# Chov2_led.net
KiCad netlist of a schematic drawn in Altium Designer
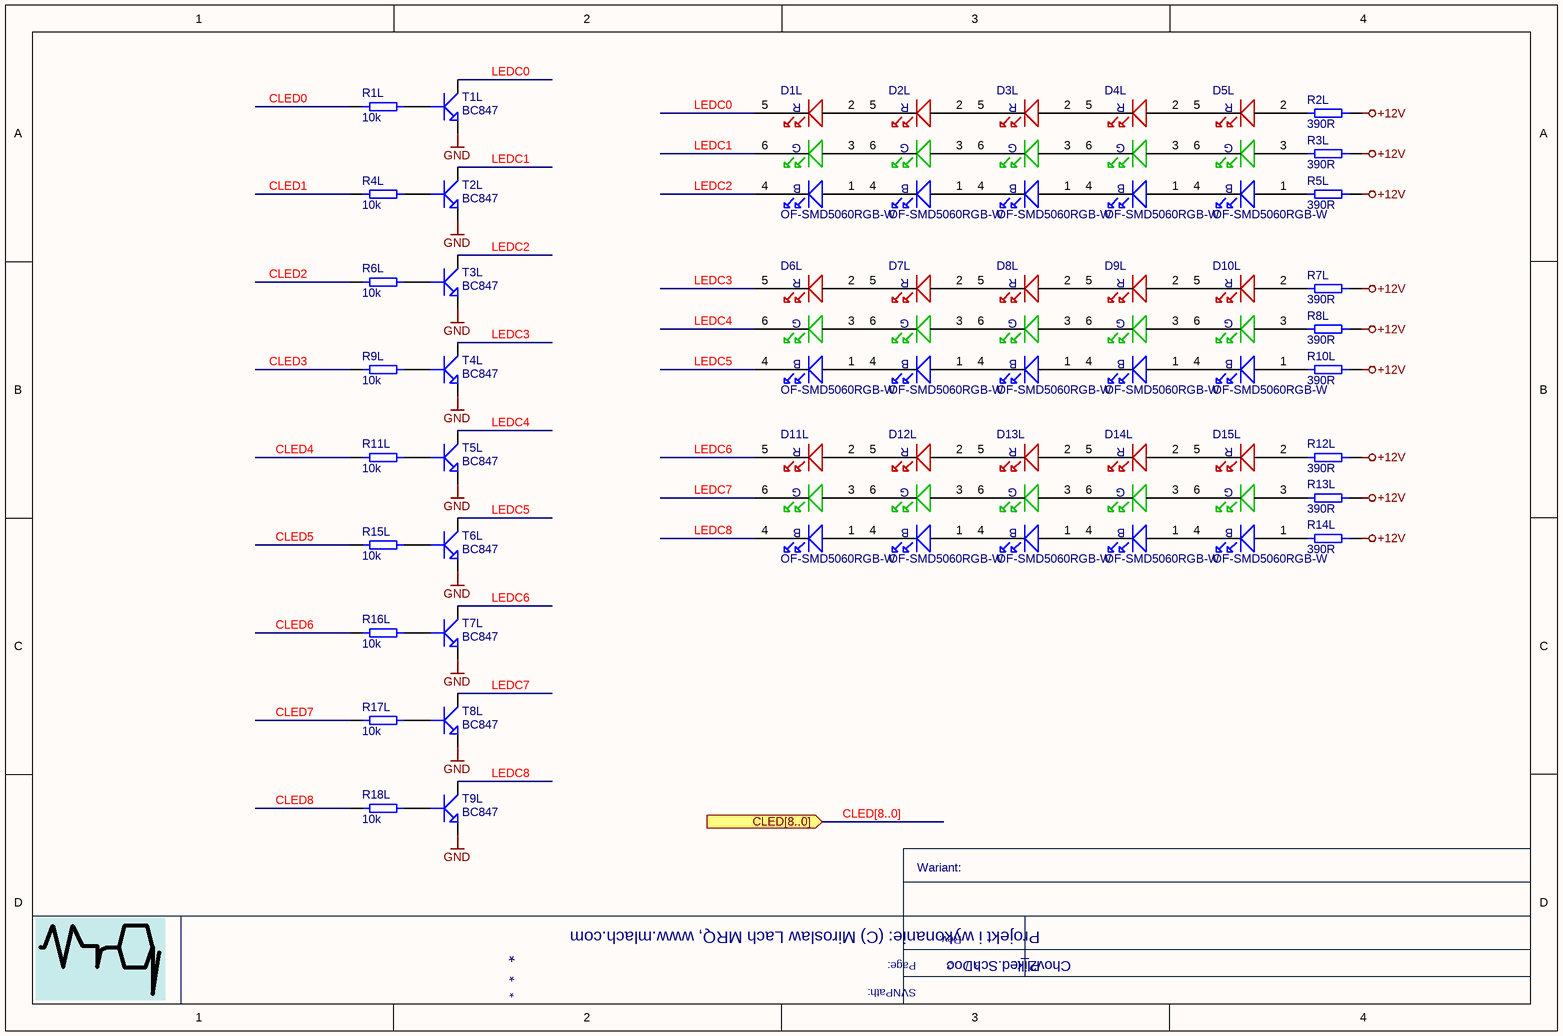
[diagram p0: Chov2_led.SchDoc]

(export (version "E")
  (design (tool "Eeschema 10.0.6"))
  (components
    (comp (ref "D1L")
      (value "OF-SMD5060RGB-W")
      (footprint "OF-SMD5060RGB-W")
      (libsource (lib "Parts") (part "OF-SMD5060RGB-W"))
    )
    (comp (ref "D2L")
      (value "OF-SMD5060RGB-W")
      (footprint "OF-SMD5060RGB-W")
      (libsource (lib "Parts") (part "OF-SMD5060RGB-W"))
    )
    (comp (ref "D3L")
      (value "OF-SMD5060RGB-W")
      (footprint "OF-SMD5060RGB-W")
      (libsource (lib "Parts") (part "OF-SMD5060RGB-W"))
    )
    (comp (ref "D4L")
      (value "OF-SMD5060RGB-W")
      (footprint "OF-SMD5060RGB-W")
      (libsource (lib "Parts") (part "OF-SMD5060RGB-W"))
    )
    (comp (ref "D5L")
      (value "OF-SMD5060RGB-W")
      (footprint "OF-SMD5060RGB-W")
      (libsource (lib "Parts") (part "OF-SMD5060RGB-W"))
    )
    (comp (ref "D6L")
      (value "OF-SMD5060RGB-W")
      (footprint "OF-SMD5060RGB-W")
      (libsource (lib "Parts") (part "OF-SMD5060RGB-W"))
    )
    (comp (ref "D7L")
      (value "OF-SMD5060RGB-W")
      (footprint "OF-SMD5060RGB-W")
      (libsource (lib "Parts") (part "OF-SMD5060RGB-W"))
    )
    (comp (ref "D8L")
      (value "OF-SMD5060RGB-W")
      (footprint "OF-SMD5060RGB-W")
      (libsource (lib "Parts") (part "OF-SMD5060RGB-W"))
    )
    (comp (ref "D9L")
      (value "OF-SMD5060RGB-W")
      (footprint "OF-SMD5060RGB-W")
      (libsource (lib "Parts") (part "OF-SMD5060RGB-W"))
    )
    (comp (ref "D10L")
      (value "OF-SMD5060RGB-W")
      (footprint "OF-SMD5060RGB-W")
      (libsource (lib "Parts") (part "OF-SMD5060RGB-W"))
    )
    (comp (ref "D11L")
      (value "OF-SMD5060RGB-W")
      (footprint "OF-SMD5060RGB-W")
      (libsource (lib "Parts") (part "OF-SMD5060RGB-W"))
    )
    (comp (ref "D12L")
      (value "OF-SMD5060RGB-W")
      (footprint "OF-SMD5060RGB-W")
      (libsource (lib "Parts") (part "OF-SMD5060RGB-W"))
    )
    (comp (ref "D13L")
      (value "OF-SMD5060RGB-W")
      (footprint "OF-SMD5060RGB-W")
      (libsource (lib "Parts") (part "OF-SMD5060RGB-W"))
    )
    (comp (ref "D14L")
      (value "OF-SMD5060RGB-W")
      (footprint "OF-SMD5060RGB-W")
      (libsource (lib "Parts") (part "OF-SMD5060RGB-W"))
    )
    (comp (ref "D15L")
      (value "OF-SMD5060RGB-W")
      (footprint "OF-SMD5060RGB-W")
      (libsource (lib "Parts") (part "OF-SMD5060RGB-W"))
    )
    (comp (ref "R1L")
      (value "0603WGF10KT5E")
      (footprint "0603-IPC")
      (fields (field (name "OTHERPARAMS") "10k") (field (name "TOLERANCE") "1%"))
      (libsource (lib "Parts") (part "R"))
    )
    (comp (ref "R2L")
      (value "0805WAF 390R T5E")
      (footprint "0805")
      (fields (field (name "OTHERPARAMS") "390R") (field (name "TOLERANCE") "1%"))
      (libsource (lib "Parts") (part "R"))
    )
    (comp (ref "R3L")
      (value "0805WAF 390R T5E")
      (footprint "0805")
      (fields (field (name "OTHERPARAMS") "390R") (field (name "TOLERANCE") "1%"))
      (libsource (lib "Parts") (part "R"))
    )
    (comp (ref "R4L")
      (value "0603WGF10KT5E")
      (footprint "0603-IPC")
      (fields (field (name "OTHERPARAMS") "10k") (field (name "TOLERANCE") "1%"))
      (libsource (lib "Parts") (part "R"))
    )
    (comp (ref "R5L")
      (value "0805WAF 390R T5E")
      (footprint "0805")
      (fields (field (name "OTHERPARAMS") "390R") (field (name "TOLERANCE") "1%"))
      (libsource (lib "Parts") (part "R"))
    )
    (comp (ref "R6L")
      (value "0603WGF10KT5E")
      (footprint "0603-IPC")
      (fields (field (name "OTHERPARAMS") "10k") (field (name "TOLERANCE") "1%"))
      (libsource (lib "Parts") (part "R"))
    )
    (comp (ref "R7L")
      (value "0805WAF 390R T5E")
      (footprint "0805")
      (fields (field (name "OTHERPARAMS") "390R") (field (name "TOLERANCE") "1%"))
      (libsource (lib "Parts") (part "R"))
    )
    (comp (ref "R8L")
      (value "0805WAF 390R T5E")
      (footprint "0805")
      (fields (field (name "OTHERPARAMS") "390R") (field (name "TOLERANCE") "1%"))
      (libsource (lib "Parts") (part "R"))
    )
    (comp (ref "R9L")
      (value "0603WGF10KT5E")
      (footprint "0603-IPC")
      (fields (field (name "OTHERPARAMS") "10k") (field (name "TOLERANCE") "1%"))
      (libsource (lib "Parts") (part "R"))
    )
    (comp (ref "R10L")
      (value "0805WAF 390R T5E")
      (footprint "0805")
      (fields (field (name "OTHERPARAMS") "390R") (field (name "TOLERANCE") "1%"))
      (libsource (lib "Parts") (part "R"))
    )
    (comp (ref "R11L")
      (value "0603WGF10KT5E")
      (footprint "0603-IPC")
      (fields (field (name "OTHERPARAMS") "10k") (field (name "TOLERANCE") "1%"))
      (libsource (lib "Parts") (part "R"))
    )
    (comp (ref "R12L")
      (value "0805WAF 390R T5E")
      (footprint "0805")
      (fields (field (name "OTHERPARAMS") "390R") (field (name "TOLERANCE") "1%"))
      (libsource (lib "Parts") (part "R"))
    )
    (comp (ref "R13L")
      (value "0805WAF 390R T5E")
      (footprint "0805")
      (fields (field (name "OTHERPARAMS") "390R") (field (name "TOLERANCE") "1%"))
      (libsource (lib "Parts") (part "R"))
    )
    (comp (ref "R14L")
      (value "0805WAF 390R T5E")
      (footprint "0805")
      (fields (field (name "OTHERPARAMS") "390R") (field (name "TOLERANCE") "1%"))
      (libsource (lib "Parts") (part "R"))
    )
    (comp (ref "R15L")
      (value "0603WGF10KT5E")
      (footprint "0603-IPC")
      (fields (field (name "OTHERPARAMS") "10k") (field (name "TOLERANCE") "1%"))
      (libsource (lib "Parts") (part "R"))
    )
    (comp (ref "R16L")
      (value "0603WGF10KT5E")
      (footprint "0603-IPC")
      (fields (field (name "OTHERPARAMS") "10k") (field (name "TOLERANCE") "1%"))
      (libsource (lib "Parts") (part "R"))
    )
    (comp (ref "R17L")
      (value "0603WGF10KT5E")
      (footprint "0603-IPC")
      (fields (field (name "OTHERPARAMS") "10k") (field (name "TOLERANCE") "1%"))
      (libsource (lib "Parts") (part "R"))
    )
    (comp (ref "R18L")
      (value "0603WGF10KT5E")
      (footprint "0603-IPC")
      (fields (field (name "OTHERPARAMS") "10k") (field (name "TOLERANCE") "1%"))
      (libsource (lib "Parts") (part "R"))
    )
    (comp (ref "T1L") (value "BC847") (footprint "SOT23-3") (libsource (lib "Parts") (part "NPN_SOT23-3")))
    (comp (ref "T2L") (value "BC847") (footprint "SOT23-3") (libsource (lib "Parts") (part "NPN_SOT23-3")))
    (comp (ref "T3L") (value "BC847") (footprint "SOT23-3") (libsource (lib "Parts") (part "NPN_SOT23-3")))
    (comp (ref "T4L") (value "BC847") (footprint "SOT23-3") (libsource (lib "Parts") (part "NPN_SOT23-3")))
    (comp (ref "T5L") (value "BC847") (footprint "SOT23-3") (libsource (lib "Parts") (part "NPN_SOT23-3")))
    (comp (ref "T6L") (value "BC847") (footprint "SOT23-3") (libsource (lib "Parts") (part "NPN_SOT23-3")))
    (comp (ref "T7L") (value "BC847") (footprint "SOT23-3") (libsource (lib "Parts") (part "NPN_SOT23-3")))
    (comp (ref "T8L") (value "BC847") (footprint "SOT23-3") (libsource (lib "Parts") (part "NPN_SOT23-3")))
    (comp (ref "T9L") (value "BC847") (footprint "SOT23-3") (libsource (lib "Parts") (part "NPN_SOT23-3")))
  )
  (nets
    (net (code "1") (name "+12V") (class "Default")
      (node (ref "R10L") (pin "2") (pinfunction "2_2") (pintype "passive"))
      (node (ref "R12L") (pin "2") (pinfunction "2_2") (pintype "passive"))
      (node (ref "R13L") (pin "2") (pinfunction "2_2") (pintype "passive"))
      (node (ref "R14L") (pin "2") (pinfunction "2_2") (pintype "passive"))
      (node (ref "R2L") (pin "2") (pinfunction "2_2") (pintype "passive"))
      (node (ref "R3L") (pin "2") (pinfunction "2_2") (pintype "passive"))
      (node (ref "R5L") (pin "2") (pinfunction "2_2") (pintype "passive"))
      (node (ref "R7L") (pin "2") (pinfunction "2_2") (pintype "passive"))
      (node (ref "R8L") (pin "2") (pinfunction "2_2") (pintype "passive"))
    )
    (net (code "2") (name "/CLED0") (class "Default")
      (node (ref "R1L") (pin "1") (pinfunction "1_1") (pintype "passive"))
    )
    (net (code "3") (name "/CLED1") (class "Default")
      (node (ref "R4L") (pin "1") (pinfunction "1_1") (pintype "passive"))
    )
    (net (code "4") (name "/CLED2") (class "Default")
      (node (ref "R6L") (pin "1") (pinfunction "1_1") (pintype "passive"))
    )
    (net (code "5") (name "/CLED3") (class "Default")
      (node (ref "R9L") (pin "1") (pinfunction "1_1") (pintype "passive"))
    )
    (net (code "6") (name "/CLED4") (class "Default")
      (node (ref "R11L") (pin "1") (pinfunction "1_1") (pintype "passive"))
    )
    (net (code "7") (name "/CLED5") (class "Default")
      (node (ref "R15L") (pin "1") (pinfunction "1_1") (pintype "passive"))
    )
    (net (code "8") (name "/CLED6") (class "Default")
      (node (ref "R16L") (pin "1") (pinfunction "1_1") (pintype "passive"))
    )
    (net (code "9") (name "/CLED7") (class "Default")
      (node (ref "R17L") (pin "1") (pinfunction "1_1") (pintype "passive"))
    )
    (net (code "10") (name "/CLED8") (class "Default")
      (node (ref "R18L") (pin "1") (pinfunction "1_1") (pintype "passive"))
    )
    (net (code "12") (name "/LEDC0") (class "Default")
      (node (ref "D1L") (pin "5") (pinfunction "CATH_5") (pintype "passive"))
      (node (ref "T1L") (pin "3") (pinfunction "3_3") (pintype "passive"))
    )
    (net (code "13") (name "/LEDC1") (class "Default")
      (node (ref "D1L") (pin "6") (pinfunction "CATH_6") (pintype "passive"))
      (node (ref "T2L") (pin "3") (pinfunction "3_3") (pintype "passive"))
    )
    (net (code "14") (name "/LEDC2") (class "Default")
      (node (ref "D1L") (pin "4") (pinfunction "CATH_4") (pintype "passive"))
      (node (ref "T3L") (pin "3") (pinfunction "3_3") (pintype "passive"))
    )
    (net (code "15") (name "/LEDC3") (class "Default")
      (node (ref "D6L") (pin "5") (pinfunction "CATH_5") (pintype "passive"))
      (node (ref "T4L") (pin "3") (pinfunction "3_3") (pintype "passive"))
    )
    (net (code "16") (name "/LEDC4") (class "Default")
      (node (ref "D6L") (pin "6") (pinfunction "CATH_6") (pintype "passive"))
      (node (ref "T5L") (pin "3") (pinfunction "3_3") (pintype "passive"))
    )
    (net (code "17") (name "/LEDC5") (class "Default")
      (node (ref "D6L") (pin "4") (pinfunction "CATH_4") (pintype "passive"))
      (node (ref "T6L") (pin "3") (pinfunction "3_3") (pintype "passive"))
    )
    (net (code "18") (name "/LEDC6") (class "Default")
      (node (ref "D11L") (pin "5") (pinfunction "CATH_5") (pintype "passive"))
      (node (ref "T7L") (pin "3") (pinfunction "3_3") (pintype "passive"))
    )
    (net (code "19") (name "/LEDC7") (class "Default")
      (node (ref "D11L") (pin "6") (pinfunction "CATH_6") (pintype "passive"))
      (node (ref "T8L") (pin "3") (pinfunction "3_3") (pintype "passive"))
    )
    (net (code "20") (name "/LEDC8") (class "Default")
      (node (ref "D11L") (pin "4") (pinfunction "CATH_4") (pintype "passive"))
      (node (ref "T9L") (pin "3") (pinfunction "3_3") (pintype "passive"))
    )
    (net (code "21") (name "GND") (class "Default")
      (node (ref "T1L") (pin "2") (pinfunction "2_2") (pintype "passive"))
      (node (ref "T2L") (pin "2") (pinfunction "2_2") (pintype "passive"))
      (node (ref "T3L") (pin "2") (pinfunction "2_2") (pintype "passive"))
      (node (ref "T4L") (pin "2") (pinfunction "2_2") (pintype "passive"))
      (node (ref "T5L") (pin "2") (pinfunction "2_2") (pintype "passive"))
      (node (ref "T6L") (pin "2") (pinfunction "2_2") (pintype "passive"))
      (node (ref "T7L") (pin "2") (pinfunction "2_2") (pintype "passive"))
      (node (ref "T8L") (pin "2") (pinfunction "2_2") (pintype "passive"))
      (node (ref "T9L") (pin "2") (pinfunction "2_2") (pintype "passive"))
    )
    (net (code "22") (name "Net-(D1L-ANOD-Pad1)") (class "Default")
      (node (ref "D1L") (pin "1") (pinfunction "ANOD_1") (pintype "passive"))
      (node (ref "D2L") (pin "4") (pinfunction "CATH_4") (pintype "passive"))
    )
    (net (code "23") (name "Net-(D1L-ANOD-Pad2)") (class "Default")
      (node (ref "D1L") (pin "2") (pinfunction "ANOD_2") (pintype "passive"))
      (node (ref "D2L") (pin "5") (pinfunction "CATH_5") (pintype "passive"))
    )
    (net (code "24") (name "Net-(D1L-ANOD-Pad3)") (class "Default")
      (node (ref "D1L") (pin "3") (pinfunction "ANOD_3") (pintype "passive"))
      (node (ref "D2L") (pin "6") (pinfunction "CATH_6") (pintype "passive"))
    )
    (net (code "25") (name "Net-(D2L-ANOD-Pad1)") (class "Default")
      (node (ref "D2L") (pin "1") (pinfunction "ANOD_1") (pintype "passive"))
      (node (ref "D3L") (pin "4") (pinfunction "CATH_4") (pintype "passive"))
    )
    (net (code "26") (name "Net-(D2L-ANOD-Pad2)") (class "Default")
      (node (ref "D2L") (pin "2") (pinfunction "ANOD_2") (pintype "passive"))
      (node (ref "D3L") (pin "5") (pinfunction "CATH_5") (pintype "passive"))
    )
    (net (code "27") (name "Net-(D2L-ANOD-Pad3)") (class "Default")
      (node (ref "D2L") (pin "3") (pinfunction "ANOD_3") (pintype "passive"))
      (node (ref "D3L") (pin "6") (pinfunction "CATH_6") (pintype "passive"))
    )
    (net (code "28") (name "Net-(D3L-ANOD-Pad1)") (class "Default")
      (node (ref "D3L") (pin "1") (pinfunction "ANOD_1") (pintype "passive"))
      (node (ref "D4L") (pin "4") (pinfunction "CATH_4") (pintype "passive"))
    )
    (net (code "29") (name "Net-(D3L-ANOD-Pad2)") (class "Default")
      (node (ref "D3L") (pin "2") (pinfunction "ANOD_2") (pintype "passive"))
      (node (ref "D4L") (pin "5") (pinfunction "CATH_5") (pintype "passive"))
    )
    (net (code "30") (name "Net-(D3L-ANOD-Pad3)") (class "Default")
      (node (ref "D3L") (pin "3") (pinfunction "ANOD_3") (pintype "passive"))
      (node (ref "D4L") (pin "6") (pinfunction "CATH_6") (pintype "passive"))
    )
    (net (code "31") (name "Net-(D4L-ANOD-Pad1)") (class "Default")
      (node (ref "D4L") (pin "1") (pinfunction "ANOD_1") (pintype "passive"))
      (node (ref "D5L") (pin "4") (pinfunction "CATH_4") (pintype "passive"))
    )
    (net (code "32") (name "Net-(D4L-ANOD-Pad2)") (class "Default")
      (node (ref "D4L") (pin "2") (pinfunction "ANOD_2") (pintype "passive"))
      (node (ref "D5L") (pin "5") (pinfunction "CATH_5") (pintype "passive"))
    )
    (net (code "33") (name "Net-(D4L-ANOD-Pad3)") (class "Default")
      (node (ref "D4L") (pin "3") (pinfunction "ANOD_3") (pintype "passive"))
      (node (ref "D5L") (pin "6") (pinfunction "CATH_6") (pintype "passive"))
    )
    (net (code "34") (name "Net-(D5L-ANOD-Pad1)") (class "Default")
      (node (ref "D5L") (pin "1") (pinfunction "ANOD_1") (pintype "passive"))
      (node (ref "R5L") (pin "1") (pinfunction "1_1") (pintype "passive"))
    )
    (net (code "35") (name "Net-(D5L-ANOD-Pad2)") (class "Default")
      (node (ref "D5L") (pin "2") (pinfunction "ANOD_2") (pintype "passive"))
      (node (ref "R2L") (pin "1") (pinfunction "1_1") (pintype "passive"))
    )
    (net (code "36") (name "Net-(D5L-ANOD-Pad3)") (class "Default")
      (node (ref "D5L") (pin "3") (pinfunction "ANOD_3") (pintype "passive"))
      (node (ref "R3L") (pin "1") (pinfunction "1_1") (pintype "passive"))
    )
    (net (code "37") (name "Net-(D6L-ANOD-Pad1)") (class "Default")
      (node (ref "D6L") (pin "1") (pinfunction "ANOD_1") (pintype "passive"))
      (node (ref "D7L") (pin "4") (pinfunction "CATH_4") (pintype "passive"))
    )
    (net (code "38") (name "Net-(D6L-ANOD-Pad2)") (class "Default")
      (node (ref "D6L") (pin "2") (pinfunction "ANOD_2") (pintype "passive"))
      (node (ref "D7L") (pin "5") (pinfunction "CATH_5") (pintype "passive"))
    )
    (net (code "39") (name "Net-(D6L-ANOD-Pad3)") (class "Default")
      (node (ref "D6L") (pin "3") (pinfunction "ANOD_3") (pintype "passive"))
      (node (ref "D7L") (pin "6") (pinfunction "CATH_6") (pintype "passive"))
    )
    (net (code "40") (name "Net-(D7L-ANOD-Pad1)") (class "Default")
      (node (ref "D7L") (pin "1") (pinfunction "ANOD_1") (pintype "passive"))
      (node (ref "D8L") (pin "4") (pinfunction "CATH_4") (pintype "passive"))
    )
    (net (code "41") (name "Net-(D7L-ANOD-Pad2)") (class "Default")
      (node (ref "D7L") (pin "2") (pinfunction "ANOD_2") (pintype "passive"))
      (node (ref "D8L") (pin "5") (pinfunction "CATH_5") (pintype "passive"))
    )
    (net (code "42") (name "Net-(D7L-ANOD-Pad3)") (class "Default")
      (node (ref "D7L") (pin "3") (pinfunction "ANOD_3") (pintype "passive"))
      (node (ref "D8L") (pin "6") (pinfunction "CATH_6") (pintype "passive"))
    )
    (net (code "43") (name "Net-(D8L-ANOD-Pad1)") (class "Default")
      (node (ref "D8L") (pin "1") (pinfunction "ANOD_1") (pintype "passive"))
      (node (ref "D9L") (pin "4") (pinfunction "CATH_4") (pintype "passive"))
    )
    (net (code "44") (name "Net-(D8L-ANOD-Pad2)") (class "Default")
      (node (ref "D8L") (pin "2") (pinfunction "ANOD_2") (pintype "passive"))
      (node (ref "D9L") (pin "5") (pinfunction "CATH_5") (pintype "passive"))
    )
    (net (code "45") (name "Net-(D8L-ANOD-Pad3)") (class "Default")
      (node (ref "D8L") (pin "3") (pinfunction "ANOD_3") (pintype "passive"))
      (node (ref "D9L") (pin "6") (pinfunction "CATH_6") (pintype "passive"))
    )
    (net (code "46") (name "Net-(D10L-ANOD-Pad1)") (class "Default")
      (node (ref "D10L") (pin "1") (pinfunction "ANOD_1") (pintype "passive"))
      (node (ref "R10L") (pin "1") (pinfunction "1_1") (pintype "passive"))
    )
    (net (code "47") (name "Net-(D10L-ANOD-Pad2)") (class "Default")
      (node (ref "D10L") (pin "2") (pinfunction "ANOD_2") (pintype "passive"))
      (node (ref "R7L") (pin "1") (pinfunction "1_1") (pintype "passive"))
    )
    (net (code "48") (name "Net-(D10L-ANOD-Pad3)") (class "Default")
      (node (ref "D10L") (pin "3") (pinfunction "ANOD_3") (pintype "passive"))
      (node (ref "R8L") (pin "1") (pinfunction "1_1") (pintype "passive"))
    )
    (net (code "49") (name "Net-(D10L-CATH-Pad4)") (class "Default")
      (node (ref "D10L") (pin "4") (pinfunction "CATH_4") (pintype "passive"))
      (node (ref "D9L") (pin "1") (pinfunction "ANOD_1") (pintype "passive"))
    )
    (net (code "50") (name "Net-(D10L-CATH-Pad5)") (class "Default")
      (node (ref "D10L") (pin "5") (pinfunction "CATH_5") (pintype "passive"))
      (node (ref "D9L") (pin "2") (pinfunction "ANOD_2") (pintype "passive"))
    )
    (net (code "51") (name "Net-(D10L-CATH-Pad6)") (class "Default")
      (node (ref "D10L") (pin "6") (pinfunction "CATH_6") (pintype "passive"))
      (node (ref "D9L") (pin "3") (pinfunction "ANOD_3") (pintype "passive"))
    )
    (net (code "52") (name "Net-(D11L-ANOD-Pad1)") (class "Default")
      (node (ref "D11L") (pin "1") (pinfunction "ANOD_1") (pintype "passive"))
      (node (ref "D12L") (pin "4") (pinfunction "CATH_4") (pintype "passive"))
    )
    (net (code "53") (name "Net-(D11L-ANOD-Pad2)") (class "Default")
      (node (ref "D11L") (pin "2") (pinfunction "ANOD_2") (pintype "passive"))
      (node (ref "D12L") (pin "5") (pinfunction "CATH_5") (pintype "passive"))
    )
    (net (code "54") (name "Net-(D11L-ANOD-Pad3)") (class "Default")
      (node (ref "D11L") (pin "3") (pinfunction "ANOD_3") (pintype "passive"))
      (node (ref "D12L") (pin "6") (pinfunction "CATH_6") (pintype "passive"))
    )
    (net (code "55") (name "Net-(D12L-ANOD-Pad1)") (class "Default")
      (node (ref "D12L") (pin "1") (pinfunction "ANOD_1") (pintype "passive"))
      (node (ref "D13L") (pin "4") (pinfunction "CATH_4") (pintype "passive"))
    )
    (net (code "56") (name "Net-(D12L-ANOD-Pad2)") (class "Default")
      (node (ref "D12L") (pin "2") (pinfunction "ANOD_2") (pintype "passive"))
      (node (ref "D13L") (pin "5") (pinfunction "CATH_5") (pintype "passive"))
    )
    (net (code "57") (name "Net-(D12L-ANOD-Pad3)") (class "Default")
      (node (ref "D12L") (pin "3") (pinfunction "ANOD_3") (pintype "passive"))
      (node (ref "D13L") (pin "6") (pinfunction "CATH_6") (pintype "passive"))
    )
    (net (code "58") (name "Net-(D13L-ANOD-Pad1)") (class "Default")
      (node (ref "D13L") (pin "1") (pinfunction "ANOD_1") (pintype "passive"))
      (node (ref "D14L") (pin "4") (pinfunction "CATH_4") (pintype "passive"))
    )
    (net (code "59") (name "Net-(D13L-ANOD-Pad2)") (class "Default")
      (node (ref "D13L") (pin "2") (pinfunction "ANOD_2") (pintype "passive"))
      (node (ref "D14L") (pin "5") (pinfunction "CATH_5") (pintype "passive"))
    )
    (net (code "60") (name "Net-(D13L-ANOD-Pad3)") (class "Default")
      (node (ref "D13L") (pin "3") (pinfunction "ANOD_3") (pintype "passive"))
      (node (ref "D14L") (pin "6") (pinfunction "CATH_6") (pintype "passive"))
    )
    (net (code "61") (name "Net-(D14L-ANOD-Pad1)") (class "Default")
      (node (ref "D14L") (pin "1") (pinfunction "ANOD_1") (pintype "passive"))
      (node (ref "D15L") (pin "4") (pinfunction "CATH_4") (pintype "passive"))
    )
    (net (code "62") (name "Net-(D14L-ANOD-Pad2)") (class "Default")
      (node (ref "D14L") (pin "2") (pinfunction "ANOD_2") (pintype "passive"))
      (node (ref "D15L") (pin "5") (pinfunction "CATH_5") (pintype "passive"))
    )
    (net (code "63") (name "Net-(D14L-ANOD-Pad3)") (class "Default")
      (node (ref "D14L") (pin "3") (pinfunction "ANOD_3") (pintype "passive"))
      (node (ref "D15L") (pin "6") (pinfunction "CATH_6") (pintype "passive"))
    )
    (net (code "64") (name "Net-(D15L-ANOD-Pad1)") (class "Default")
      (node (ref "D15L") (pin "1") (pinfunction "ANOD_1") (pintype "passive"))
      (node (ref "R14L") (pin "1") (pinfunction "1_1") (pintype "passive"))
    )
    (net (code "65") (name "Net-(D15L-ANOD-Pad2)") (class "Default")
      (node (ref "D15L") (pin "2") (pinfunction "ANOD_2") (pintype "passive"))
      (node (ref "R12L") (pin "1") (pinfunction "1_1") (pintype "passive"))
    )
    (net (code "66") (name "Net-(D15L-ANOD-Pad3)") (class "Default")
      (node (ref "D15L") (pin "3") (pinfunction "ANOD_3") (pintype "passive"))
      (node (ref "R13L") (pin "1") (pinfunction "1_1") (pintype "passive"))
    )
    (net (code "67") (name "Net-(R1L-Pad2)") (class "Default")
      (node (ref "R1L") (pin "2") (pinfunction "2_2") (pintype "passive"))
      (node (ref "T1L") (pin "1") (pinfunction "1_1") (pintype "passive"))
    )
    (net (code "68") (name "Net-(R4L-Pad2)") (class "Default")
      (node (ref "R4L") (pin "2") (pinfunction "2_2") (pintype "passive"))
      (node (ref "T2L") (pin "1") (pinfunction "1_1") (pintype "passive"))
    )
    (net (code "69") (name "Net-(R6L-Pad2)") (class "Default")
      (node (ref "R6L") (pin "2") (pinfunction "2_2") (pintype "passive"))
      (node (ref "T3L") (pin "1") (pinfunction "1_1") (pintype "passive"))
    )
    (net (code "70") (name "Net-(R9L-Pad2)") (class "Default")
      (node (ref "R9L") (pin "2") (pinfunction "2_2") (pintype "passive"))
      (node (ref "T4L") (pin "1") (pinfunction "1_1") (pintype "passive"))
    )
    (net (code "71") (name "Net-(R11L-Pad2)") (class "Default")
      (node (ref "R11L") (pin "2") (pinfunction "2_2") (pintype "passive"))
      (node (ref "T5L") (pin "1") (pinfunction "1_1") (pintype "passive"))
    )
    (net (code "72") (name "Net-(R15L-Pad2)") (class "Default")
      (node (ref "R15L") (pin "2") (pinfunction "2_2") (pintype "passive"))
      (node (ref "T6L") (pin "1") (pinfunction "1_1") (pintype "passive"))
    )
    (net (code "73") (name "Net-(R16L-Pad2)") (class "Default")
      (node (ref "R16L") (pin "2") (pinfunction "2_2") (pintype "passive"))
      (node (ref "T7L") (pin "1") (pinfunction "1_1") (pintype "passive"))
    )
    (net (code "74") (name "Net-(R17L-Pad2)") (class "Default")
      (node (ref "R17L") (pin "2") (pinfunction "2_2") (pintype "passive"))
      (node (ref "T8L") (pin "1") (pinfunction "1_1") (pintype "passive"))
    )
    (net (code "75") (name "Net-(R18L-Pad2)") (class "Default")
      (node (ref "R18L") (pin "2") (pinfunction "2_2") (pintype "passive"))
      (node (ref "T9L") (pin "1") (pinfunction "1_1") (pintype "passive"))
    )
  )
)
